# SCH__Atlas_2026-06-21.net
KiCad netlist of a schematic drawn in EasyEDA
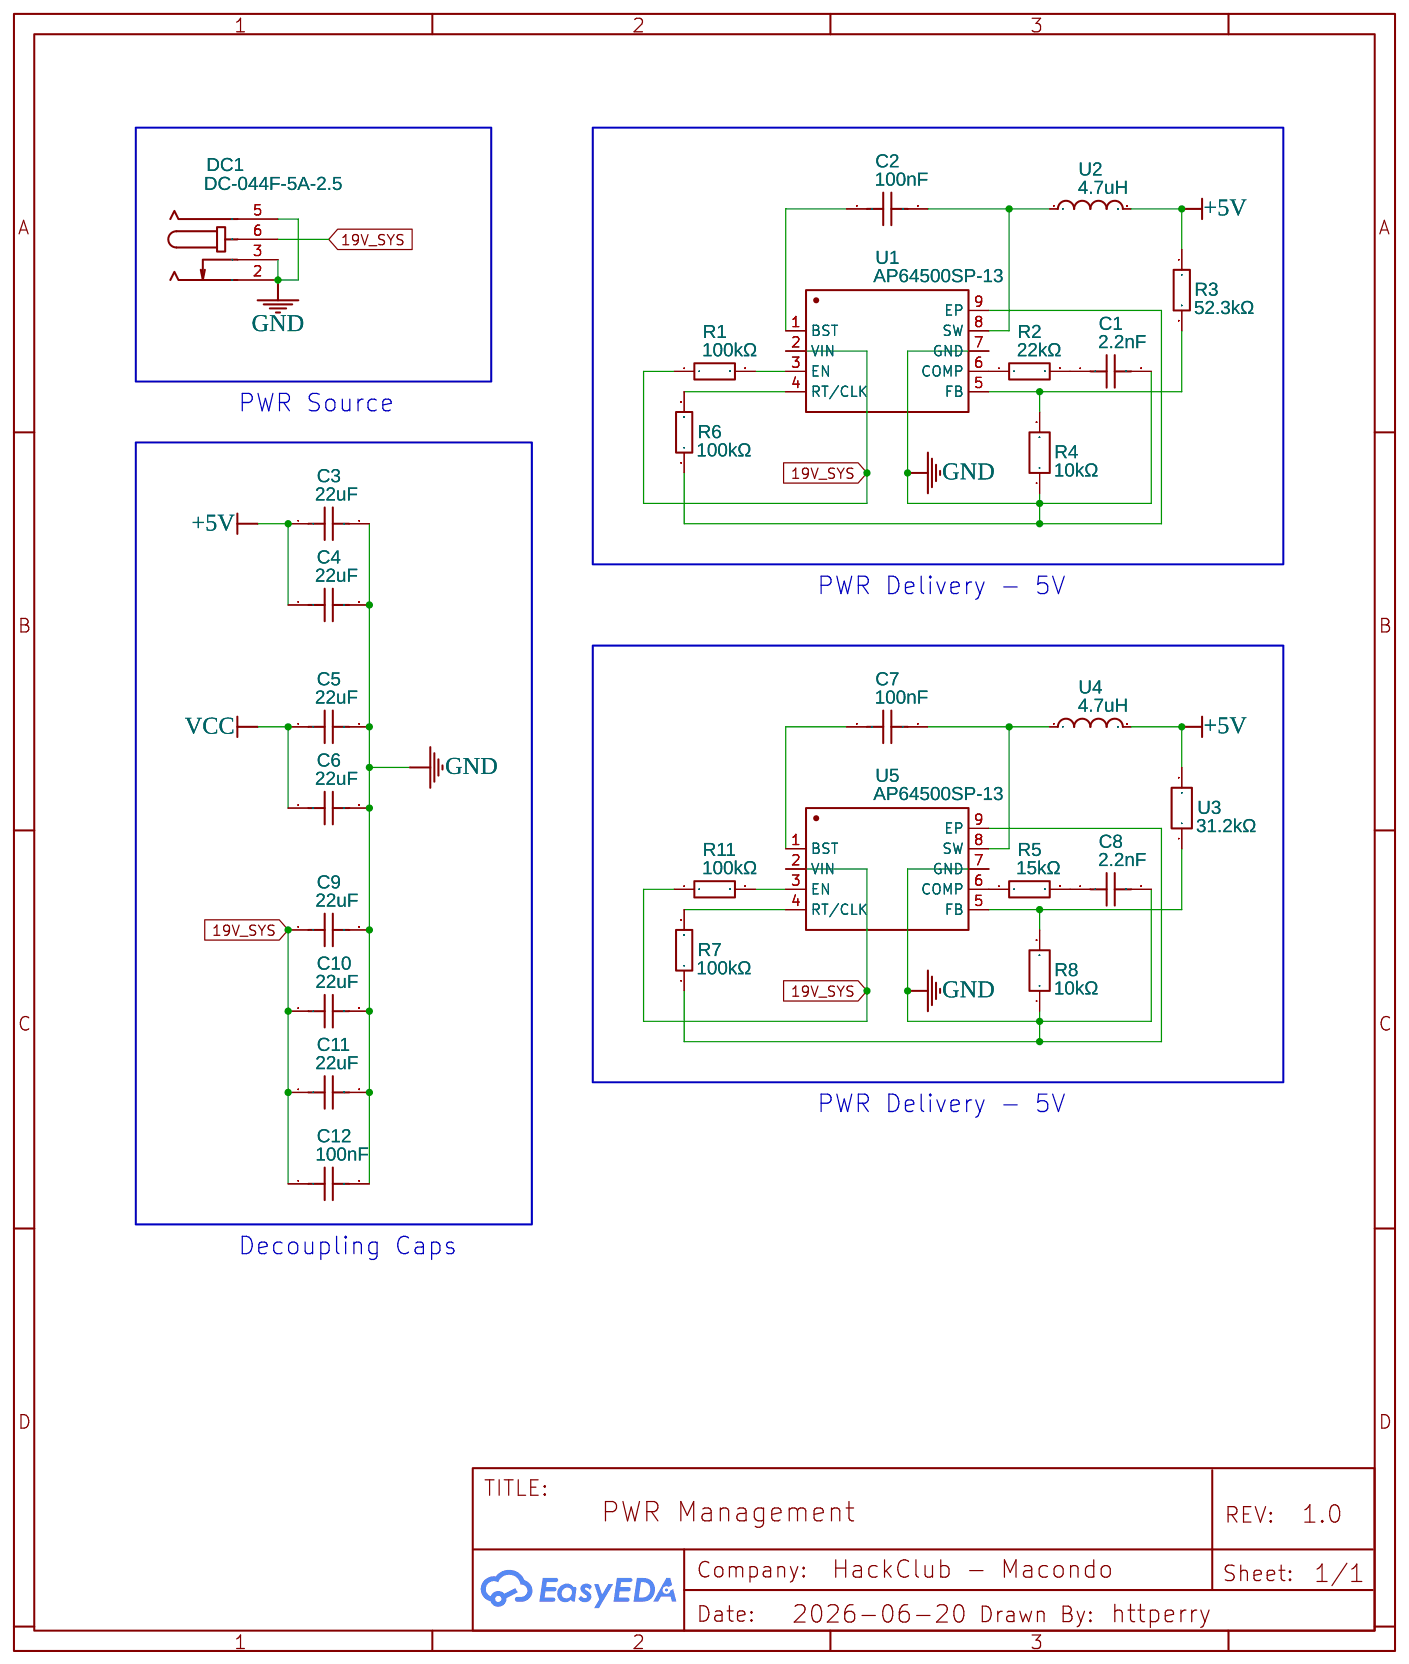
[diagram p0: schematic sheet]

(export (version "E")
  (design (tool "Eeschema 10.0.6"))
  (components
    (comp (ref "C1")
      (value "2.2nF")
      (fields
        (field (name "Manufacturer Part") "FCC0603B222K500CT")
        (field (name "Manufacturer") "FOJAN(富捷)")
      )
      (libsource (lib "") (part "FCC0603B222K500CT"))
    )
    (comp (ref "C2")
      (value "100nF")
      (fields
        (field (name "Manufacturer Part") "GRM188R71H104KA93D")
        (field (name "Manufacturer") "muRata(村田)")
      )
      (libsource (lib "") (part "GRM188R71H104KA93D"))
    )
    (comp (ref "C3")
      (value "22uF")
      (fields
        (field (name "Manufacturer Part") "HGC0603R5226M160NTHJ")
        (field (name "Manufacturer") "Chinocera(华瓷)")
      )
      (libsource (lib "") (part "HGC0603R5226M160NTHJ"))
    )
    (comp (ref "C4")
      (value "22uF")
      (fields
        (field (name "Manufacturer Part") "HGC0603R5226M160NTHJ")
        (field (name "Manufacturer") "Chinocera(华瓷)")
      )
      (libsource (lib "") (part "HGC0603R5226M160NTHJ"))
    )
    (comp (ref "C5")
      (value "22uF")
      (fields
        (field (name "Manufacturer Part") "HGC0603R5226M160NTHJ")
        (field (name "Manufacturer") "Chinocera(华瓷)")
      )
      (libsource (lib "") (part "HGC0603R5226M160NTHJ"))
    )
    (comp (ref "C6")
      (value "22uF")
      (fields
        (field (name "Manufacturer Part") "HGC0603R5226M160NTHJ")
        (field (name "Manufacturer") "Chinocera(华瓷)")
      )
      (libsource (lib "") (part "HGC0603R5226M160NTHJ"))
    )
    (comp (ref "C7")
      (value "100nF")
      (fields
        (field (name "Manufacturer Part") "GRM188R71H104KA93D")
        (field (name "Manufacturer") "muRata(村田)")
      )
      (libsource (lib "") (part "GRM188R71H104KA93D"))
    )
    (comp (ref "C8")
      (value "2.2nF")
      (fields
        (field (name "Manufacturer Part") "FCC0603B222K500CT")
        (field (name "Manufacturer") "FOJAN(富捷)")
      )
      (libsource (lib "") (part "FCC0603B222K500CT"))
    )
    (comp (ref "C9")
      (value "22uF")
      (fields
        (field (name "Manufacturer Part") "KCM55QR71H226KH13K")
        (field (name "Manufacturer") "muRata(村田)")
      )
      (libsource (lib "") (part "KCM55QR71H226KH13K"))
    )
    (comp (ref "C10")
      (value "22uF")
      (fields
        (field (name "Manufacturer Part") "KCM55QR71H226KH13K")
        (field (name "Manufacturer") "muRata(村田)")
      )
      (libsource (lib "") (part "KCM55QR71H226KH13K"))
    )
    (comp (ref "C11")
      (value "22uF")
      (fields
        (field (name "Manufacturer Part") "KCM55QR71H226KH13K")
        (field (name "Manufacturer") "muRata(村田)")
      )
      (libsource (lib "") (part "KCM55QR71H226KH13K"))
    )
    (comp (ref "C12")
      (value "100nF")
      (fields
        (field (name "Manufacturer Part") "GRM188R71H104KA93D")
        (field (name "Manufacturer") "muRata(村田)")
      )
      (libsource (lib "") (part "GRM188R71H104KA93D"))
    )
    (comp (ref "DC1")
      (value "DC-044F-5A-2.5")
      (fields (field (name "Manufacturer") "XKB Connection(中国星坤)"))
      (libsource (lib "") (part "DC-044F-5A-2.5"))
    )
    (comp (ref "R1")
      (value "100kΩ")
      (fields (field (name "Manufacturer Part") "RS-03K1003FT") (field (name "Manufacturer") "FH(风华)"))
      (libsource (lib "") (part "RS-03K1003FT_C115320"))
    )
    (comp (ref "R2")
      (value "22kΩ")
      (fields (field (name "Manufacturer Part") "RS-03K2202FT") (field (name "Manufacturer") "FH(风华)"))
      (libsource (lib "") (part "RS-03K2202FT"))
    )
    (comp (ref "R3")
      (value "52.3kΩ")
      (fields (field (name "Manufacturer Part") "RS-03K5232FT") (field (name "Manufacturer") "FH(风华)"))
      (libsource (lib "") (part "RS-03K5232FT"))
    )
    (comp (ref "R4")
      (value "10kΩ")
      (fields (field (name "Manufacturer Part") "AR03BTS1002") (field (name "Manufacturer") "Viking(光颉)"))
      (libsource (lib "") (part "AR03BTS1002"))
    )
    (comp (ref "R5")
      (value "15kΩ")
      (fields (field (name "Manufacturer Part") "CR0603FA1502G") (field (name "Manufacturer") "LIZ(丽智电子)"))
      (libsource (lib "") (part "CR0603FA1502G"))
    )
    (comp (ref "R6")
      (value "100kΩ")
      (fields (field (name "Manufacturer Part") "RS-03K1003FT") (field (name "Manufacturer") "FH(风华)"))
      (libsource (lib "") (part "RS-03K1003FT_C115320_1"))
    )
    (comp (ref "R7")
      (value "100kΩ")
      (fields (field (name "Manufacturer Part") "RS-03K1003FT") (field (name "Manufacturer") "FH(风华)"))
      (libsource (lib "") (part "RS-03K1003FT_C115320_1"))
    )
    (comp (ref "R8")
      (value "10kΩ")
      (fields (field (name "Manufacturer Part") "AR03BTS1002") (field (name "Manufacturer") "Viking(光颉)"))
      (libsource (lib "") (part "AR03BTS1002"))
    )
    (comp (ref "R11")
      (value "100kΩ")
      (fields (field (name "Manufacturer Part") "RS-03K1003FT") (field (name "Manufacturer") "FH(风华)"))
      (libsource (lib "") (part "RS-03K1003FT_C115320"))
    )
    (comp (ref "U1")
      (value "AP64500SP-13")
      (fields (field (name "Manufacturer") "DIODES(美台)"))
      (libsource (lib "") (part "AP64500SP-13"))
    )
    (comp (ref "U2")
      (value "4.7uH")
      (fields (field (name "Manufacturer Part") "APH0630T4R7M") (field (name "Manufacturer") "APV(爱普微)"))
      (libsource (lib "") (part "APH0630T4R7M"))
    )
    (comp (ref "U3")
      (value "31.2kΩ")
      (fields (field (name "Manufacturer Part") "RT0603DRE0731K2L") (field (name "Manufacturer") "YAGEO(国巨)"))
      (libsource (lib "") (part "RT0603DRE0731K2L"))
    )
    (comp (ref "U4")
      (value "4.7uH")
      (fields (field (name "Manufacturer Part") "APH0630T4R7M") (field (name "Manufacturer") "APV(爱普微)"))
      (libsource (lib "") (part "APH0630T4R7M"))
    )
    (comp (ref "U5")
      (value "AP64500SP-13")
      (fields (field (name "Manufacturer") "DIODES(美台)"))
      (libsource (lib "") (part "AP64500SP-13"))
    )
  )
  (nets
    (net (code "1") (name "+5V") (class "Default")
      (node (ref "C3") (pin "1") (pinfunction "1_1") (pintype "unspecified"))
      (node (ref "C4") (pin "1") (pinfunction "1_1") (pintype "unspecified"))
      (node (ref "R3") (pin "1") (pinfunction "1_1") (pintype "unspecified"))
      (node (ref "U2") (pin "2") (pinfunction "2_2") (pintype "unspecified"))
      (node (ref "U3") (pin "2") (pinfunction "2_2") (pintype "unspecified"))
      (node (ref "U4") (pin "2") (pinfunction "2_2") (pintype "unspecified"))
    )
    (net (code "2") (name "19V_SYS") (class "Default")
      (node (ref "C10") (pin "1") (pinfunction "1_1") (pintype "unspecified"))
      (node (ref "C11") (pin "1") (pinfunction "1_1") (pintype "unspecified"))
      (node (ref "C12") (pin "1") (pinfunction "1_1") (pintype "unspecified"))
      (node (ref "C9") (pin "1") (pinfunction "1_1") (pintype "unspecified"))
      (node (ref "DC1") (pin "6") (pinfunction "6_6") (pintype "unspecified"))
      (node (ref "R1") (pin "1") (pinfunction "1_1") (pintype "unspecified"))
      (node (ref "R11") (pin "1") (pinfunction "1_1") (pintype "unspecified"))
      (node (ref "U1") (pin "2") (pinfunction "VIN_2") (pintype "unspecified"))
      (node (ref "U5") (pin "2") (pinfunction "VIN_2") (pintype "unspecified"))
    )
    (net (code "3") (name "GND") (class "Default")
      (node (ref "C1") (pin "2") (pinfunction "2_2") (pintype "unspecified"))
      (node (ref "C10") (pin "2") (pinfunction "2_2") (pintype "unspecified"))
      (node (ref "C11") (pin "2") (pinfunction "2_2") (pintype "unspecified"))
      (node (ref "C12") (pin "2") (pinfunction "2_2") (pintype "unspecified"))
      (node (ref "C3") (pin "2") (pinfunction "2_2") (pintype "unspecified"))
      (node (ref "C4") (pin "2") (pinfunction "2_2") (pintype "unspecified"))
      (node (ref "C5") (pin "2") (pinfunction "2_2") (pintype "unspecified"))
      (node (ref "C6") (pin "2") (pinfunction "2_2") (pintype "unspecified"))
      (node (ref "C8") (pin "2") (pinfunction "2_2") (pintype "unspecified"))
      (node (ref "C9") (pin "2") (pinfunction "2_2") (pintype "unspecified"))
      (node (ref "DC1") (pin "2") (pinfunction "2_2") (pintype "unspecified"))
      (node (ref "DC1") (pin "3") (pinfunction "3_3") (pintype "unspecified"))
      (node (ref "DC1") (pin "5") (pinfunction "5_5") (pintype "unspecified"))
      (node (ref "R4") (pin "1") (pinfunction "1_1") (pintype "unspecified"))
      (node (ref "R6") (pin "1") (pinfunction "1_1") (pintype "unspecified"))
      (node (ref "R7") (pin "1") (pinfunction "1_1") (pintype "unspecified"))
      (node (ref "R8") (pin "1") (pinfunction "1_1") (pintype "unspecified"))
      (node (ref "U1") (pin "7") (pinfunction "GND_7") (pintype "unspecified"))
      (node (ref "U1") (pin "9") (pinfunction "EP_9") (pintype "unspecified"))
      (node (ref "U5") (pin "7") (pinfunction "GND_7") (pintype "unspecified"))
      (node (ref "U5") (pin "9") (pinfunction "EP_9") (pintype "unspecified"))
    )
    (net (code "4") (name "Net-(C1-Pad1)") (class "Default")
      (node (ref "C1") (pin "1") (pinfunction "1_1") (pintype "unspecified"))
      (node (ref "R2") (pin "2") (pinfunction "2_2") (pintype "unspecified"))
    )
    (net (code "5") (name "Net-(C8-Pad1)") (class "Default")
      (node (ref "C8") (pin "1") (pinfunction "1_1") (pintype "unspecified"))
      (node (ref "R5") (pin "2") (pinfunction "2_2") (pintype "input"))
    )
    (net (code "6") (name "Net-(U1-BST)") (class "Default")
      (node (ref "C2") (pin "1") (pinfunction "1_1") (pintype "unspecified"))
      (node (ref "U1") (pin "1") (pinfunction "BST_1") (pintype "unspecified"))
    )
    (net (code "7") (name "Net-(U1-COMP)") (class "Default")
      (node (ref "R2") (pin "1") (pinfunction "1_1") (pintype "unspecified"))
      (node (ref "U1") (pin "6") (pinfunction "COMP_6") (pintype "unspecified"))
    )
    (net (code "8") (name "Net-(U1-EN)") (class "Default")
      (node (ref "R1") (pin "2") (pinfunction "2_2") (pintype "unspecified"))
      (node (ref "U1") (pin "3") (pinfunction "EN_3") (pintype "unspecified"))
    )
    (net (code "9") (name "Net-(U1-FB)") (class "Default")
      (node (ref "R3") (pin "2") (pinfunction "2_2") (pintype "unspecified"))
      (node (ref "R4") (pin "2") (pinfunction "2_2") (pintype "unspecified"))
      (node (ref "U1") (pin "5") (pinfunction "FB_5") (pintype "unspecified"))
    )
    (net (code "10") (name "Net-(U1-RT{slash}CLK)") (class "Default")
      (node (ref "R6") (pin "2") (pinfunction "2_2") (pintype "unspecified"))
      (node (ref "U1") (pin "4") (pinfunction "RT/CLK_4") (pintype "unspecified"))
    )
    (net (code "11") (name "Net-(U1-SW)") (class "Default")
      (node (ref "C2") (pin "2") (pinfunction "2_2") (pintype "unspecified"))
      (node (ref "U1") (pin "8") (pinfunction "SW_8") (pintype "unspecified"))
      (node (ref "U2") (pin "1") (pinfunction "1_1") (pintype "unspecified"))
    )
    (net (code "12") (name "Net-(U5-BST)") (class "Default")
      (node (ref "C7") (pin "1") (pinfunction "1_1") (pintype "unspecified"))
      (node (ref "U5") (pin "1") (pinfunction "BST_1") (pintype "unspecified"))
    )
    (net (code "13") (name "Net-(U5-COMP)") (class "Default")
      (node (ref "R5") (pin "1") (pinfunction "1_1") (pintype "input"))
      (node (ref "U5") (pin "6") (pinfunction "COMP_6") (pintype "unspecified"))
    )
    (net (code "14") (name "Net-(U5-EN)") (class "Default")
      (node (ref "R11") (pin "2") (pinfunction "2_2") (pintype "unspecified"))
      (node (ref "U5") (pin "3") (pinfunction "EN_3") (pintype "unspecified"))
    )
    (net (code "15") (name "Net-(U5-FB)") (class "Default")
      (node (ref "R8") (pin "2") (pinfunction "2_2") (pintype "unspecified"))
      (node (ref "U3") (pin "1") (pinfunction "1_1") (pintype "unspecified"))
      (node (ref "U5") (pin "5") (pinfunction "FB_5") (pintype "unspecified"))
    )
    (net (code "16") (name "Net-(U5-RT{slash}CLK)") (class "Default")
      (node (ref "R7") (pin "2") (pinfunction "2_2") (pintype "unspecified"))
      (node (ref "U5") (pin "4") (pinfunction "RT/CLK_4") (pintype "unspecified"))
    )
    (net (code "17") (name "Net-(U5-SW)") (class "Default")
      (node (ref "C7") (pin "2") (pinfunction "2_2") (pintype "unspecified"))
      (node (ref "U4") (pin "1") (pinfunction "1_1") (pintype "unspecified"))
      (node (ref "U5") (pin "8") (pinfunction "SW_8") (pintype "unspecified"))
    )
    (net (code "18") (name "VCC") (class "Default")
      (node (ref "C5") (pin "1") (pinfunction "1_1") (pintype "unspecified"))
      (node (ref "C6") (pin "1") (pinfunction "1_1") (pintype "unspecified"))
    )
  )
)
